# printer_control.net
KiCad netlist of a schematic drawn in Altium Designer
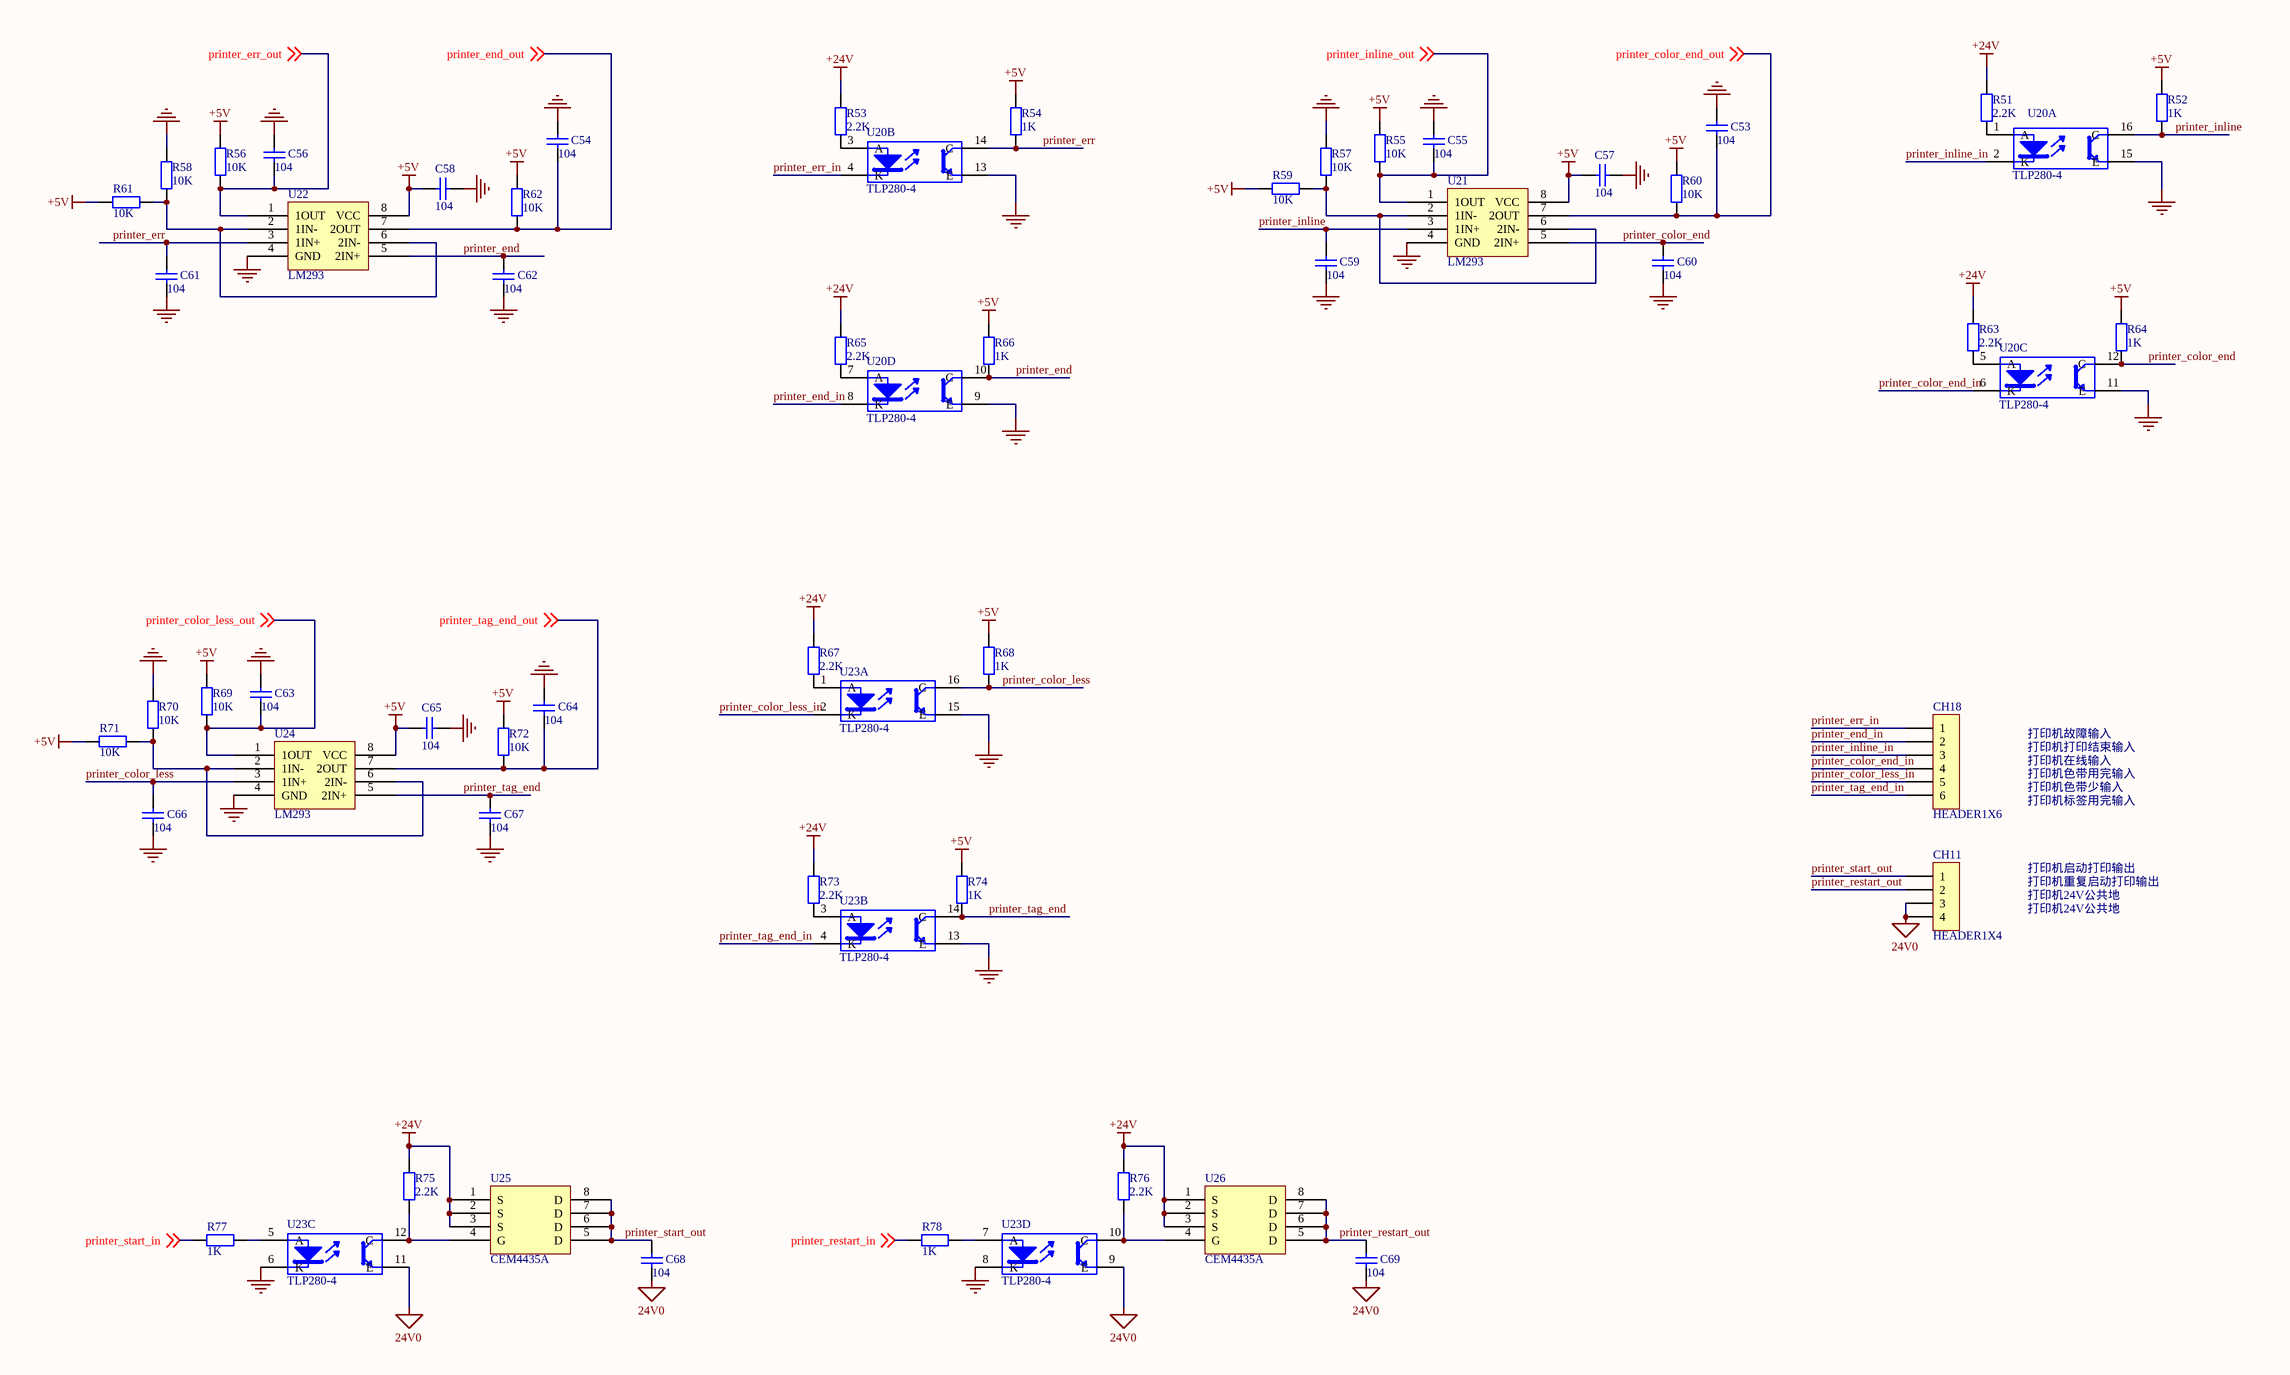
[diagram p0: printer_control.SchDoc]

(export (version "E")
  (design (tool "Eeschema 10.0.6"))
  (components
    (comp (ref "C53")
      (value "104")
      (footprint "0805")
      (description "Capacitor")
      (fields (field (name "Comment") "Cap") (field (name "PUBLISHER") "Altium Limited"))
      (libsource (lib "Miscellaneous Devices") (part "Cap"))
    )
    (comp (ref "C54")
      (value "104")
      (footprint "0805")
      (description "Capacitor")
      (fields (field (name "Comment") "Cap") (field (name "PUBLISHER") "Altium Limited"))
      (libsource (lib "Miscellaneous Devices") (part "Cap"))
    )
    (comp (ref "C55")
      (value "104")
      (footprint "0805")
      (description "Capacitor")
      (fields (field (name "Comment") "Cap") (field (name "PUBLISHER") "Altium Limited"))
      (libsource (lib "Miscellaneous Devices") (part "Cap"))
    )
    (comp (ref "C56")
      (value "104")
      (footprint "0805")
      (description "Capacitor")
      (fields (field (name "Comment") "Cap") (field (name "PUBLISHER") "Altium Limited"))
      (libsource (lib "Miscellaneous Devices") (part "Cap"))
    )
    (comp (ref "C57")
      (value "104")
      (footprint "0805")
      (description "Capacitor")
      (fields (field (name "Comment") "Cap") (field (name "PUBLISHER") "Altium Limited"))
      (libsource (lib "Miscellaneous Devices") (part "Cap"))
    )
    (comp (ref "C58")
      (value "104")
      (footprint "0805")
      (description "Capacitor")
      (fields (field (name "Comment") "Cap") (field (name "PUBLISHER") "Altium Limited"))
      (libsource (lib "Miscellaneous Devices") (part "Cap"))
    )
    (comp (ref "C59")
      (value "104")
      (footprint "0805")
      (description "Capacitor")
      (fields (field (name "Comment") "Cap") (field (name "PUBLISHER") "Altium Limited"))
      (libsource (lib "Miscellaneous Devices") (part "Cap"))
    )
    (comp (ref "C60")
      (value "104")
      (footprint "0805")
      (description "Capacitor")
      (fields (field (name "Comment") "Cap") (field (name "PUBLISHER") "Altium Limited"))
      (libsource (lib "Miscellaneous Devices") (part "Cap"))
    )
    (comp (ref "C61")
      (value "104")
      (footprint "0805")
      (description "Capacitor")
      (fields (field (name "Comment") "Cap") (field (name "PUBLISHER") "Altium Limited"))
      (libsource (lib "Miscellaneous Devices") (part "Cap"))
    )
    (comp (ref "C62")
      (value "104")
      (footprint "0805")
      (description "Capacitor")
      (fields (field (name "Comment") "Cap") (field (name "PUBLISHER") "Altium Limited"))
      (libsource (lib "Miscellaneous Devices") (part "Cap"))
    )
    (comp (ref "C63")
      (value "104")
      (footprint "0805")
      (description "Capacitor")
      (fields (field (name "Comment") "Cap") (field (name "PUBLISHER") "Altium Limited"))
      (libsource (lib "Miscellaneous Devices") (part "Cap"))
    )
    (comp (ref "C64")
      (value "104")
      (footprint "0805")
      (description "Capacitor")
      (fields (field (name "Comment") "Cap") (field (name "PUBLISHER") "Altium Limited"))
      (libsource (lib "Miscellaneous Devices") (part "Cap"))
    )
    (comp (ref "C65")
      (value "104")
      (footprint "0805")
      (description "Capacitor")
      (fields (field (name "Comment") "Cap") (field (name "PUBLISHER") "Altium Limited"))
      (libsource (lib "Miscellaneous Devices") (part "Cap"))
    )
    (comp (ref "C66")
      (value "104")
      (footprint "0805")
      (description "Capacitor")
      (fields (field (name "Comment") "Cap") (field (name "PUBLISHER") "Altium Limited"))
      (libsource (lib "Miscellaneous Devices") (part "Cap"))
    )
    (comp (ref "C67")
      (value "104")
      (footprint "0805")
      (description "Capacitor")
      (fields (field (name "Comment") "Cap") (field (name "PUBLISHER") "Altium Limited"))
      (libsource (lib "Miscellaneous Devices") (part "Cap"))
    )
    (comp (ref "C68")
      (value "104")
      (footprint "0805")
      (description "Capacitor")
      (fields (field (name "Comment") "Cap") (field (name "PUBLISHER") "Altium Limited"))
      (libsource (lib "Miscellaneous Devices") (part "Cap"))
    )
    (comp (ref "C69")
      (value "104")
      (footprint "0805")
      (description "Capacitor")
      (fields (field (name "Comment") "Cap") (field (name "PUBLISHER") "Altium Limited"))
      (libsource (lib "Miscellaneous Devices") (part "Cap"))
    )
    (comp (ref "CH11")
      (value "HEADER1X4")
      (footprint "CH3.96-4PIN")
      (libsource (lib "myIntegrated_Library1") (part "HEADER1X4"))
    )
    (comp (ref "CH18")
      (value "HEADER1X6")
      (footprint "CH3.96-6PIN")
      (libsource (lib "myIntegrated_Library1") (part "HEADER1X6"))
    )
    (comp (ref "R51")
      (value "2.2K")
      (footprint "0805")
      (description "Resistor")
      (fields (field (name "Comment") "Res2") (field (name "PUBLISHER") "Altium Limited"))
      (libsource (lib "") (part "Res2_1"))
    )
    (comp (ref "R52")
      (value "1K")
      (footprint "0805")
      (description "Resistor")
      (fields (field (name "Comment") "Res2") (field (name "PUBLISHER") "Altium Limited"))
      (libsource (lib "") (part "Res2_1"))
    )
    (comp (ref "R53")
      (value "2.2K")
      (footprint "0805")
      (description "Resistor")
      (fields (field (name "Comment") "Res2") (field (name "PUBLISHER") "Altium Limited"))
      (libsource (lib "") (part "Res2_1"))
    )
    (comp (ref "R54")
      (value "1K")
      (footprint "0805")
      (description "Resistor")
      (fields (field (name "Comment") "Res2") (field (name "PUBLISHER") "Altium Limited"))
      (libsource (lib "") (part "Res2_1"))
    )
    (comp (ref "R55")
      (value "10K")
      (footprint "0805")
      (description "Resistor")
      (fields (field (name "Comment") "Res2") (field (name "PUBLISHER") "Altium Limited"))
      (libsource (lib "") (part "Res2_1"))
    )
    (comp (ref "R56")
      (value "10K")
      (footprint "0805")
      (description "Resistor")
      (fields (field (name "Comment") "Res2") (field (name "PUBLISHER") "Altium Limited"))
      (libsource (lib "") (part "Res2_1"))
    )
    (comp (ref "R57")
      (value "10K")
      (footprint "0805")
      (description "Resistor")
      (fields (field (name "Comment") "Res2") (field (name "PUBLISHER") "Altium Limited"))
      (libsource (lib "") (part "Res2_1"))
    )
    (comp (ref "R58")
      (value "10K")
      (footprint "0805")
      (description "Resistor")
      (fields (field (name "Comment") "Res2") (field (name "PUBLISHER") "Altium Limited"))
      (libsource (lib "") (part "Res2_1"))
    )
    (comp (ref "R59")
      (value "10K")
      (footprint "0805")
      (description "Resistor")
      (fields (field (name "Comment") "Res2") (field (name "PUBLISHER") "Altium Limited"))
      (libsource (lib "Miscellaneous Devices") (part "Res2"))
    )
    (comp (ref "R60")
      (value "10K")
      (footprint "0805")
      (description "Resistor")
      (fields (field (name "Comment") "Res2") (field (name "PUBLISHER") "Altium Limited"))
      (libsource (lib "") (part "Res2_1"))
    )
    (comp (ref "R61")
      (value "10K")
      (footprint "0805")
      (description "Resistor")
      (fields (field (name "Comment") "Res2") (field (name "PUBLISHER") "Altium Limited"))
      (libsource (lib "Miscellaneous Devices") (part "Res2"))
    )
    (comp (ref "R62")
      (value "10K")
      (footprint "0805")
      (description "Resistor")
      (fields (field (name "Comment") "Res2") (field (name "PUBLISHER") "Altium Limited"))
      (libsource (lib "") (part "Res2_1"))
    )
    (comp (ref "R63")
      (value "2.2K")
      (footprint "0805")
      (description "Resistor")
      (fields (field (name "Comment") "Res2") (field (name "PUBLISHER") "Altium Limited"))
      (libsource (lib "") (part "Res2_1"))
    )
    (comp (ref "R64")
      (value "1K")
      (footprint "0805")
      (description "Resistor")
      (fields (field (name "Comment") "Res2") (field (name "PUBLISHER") "Altium Limited"))
      (libsource (lib "") (part "Res2_1"))
    )
    (comp (ref "R65")
      (value "2.2K")
      (footprint "0805")
      (description "Resistor")
      (fields (field (name "Comment") "Res2") (field (name "PUBLISHER") "Altium Limited"))
      (libsource (lib "") (part "Res2_1"))
    )
    (comp (ref "R66")
      (value "1K")
      (footprint "0805")
      (description "Resistor")
      (fields (field (name "Comment") "Res2") (field (name "PUBLISHER") "Altium Limited"))
      (libsource (lib "") (part "Res2_1"))
    )
    (comp (ref "R67")
      (value "2.2K")
      (footprint "0805")
      (description "Resistor")
      (fields (field (name "Comment") "Res2") (field (name "PUBLISHER") "Altium Limited"))
      (libsource (lib "") (part "Res2_1"))
    )
    (comp (ref "R68")
      (value "1K")
      (footprint "0805")
      (description "Resistor")
      (fields (field (name "Comment") "Res2") (field (name "PUBLISHER") "Altium Limited"))
      (libsource (lib "") (part "Res2_1"))
    )
    (comp (ref "R69")
      (value "10K")
      (footprint "0805")
      (description "Resistor")
      (fields (field (name "Comment") "Res2") (field (name "PUBLISHER") "Altium Limited"))
      (libsource (lib "") (part "Res2_1"))
    )
    (comp (ref "R70")
      (value "10K")
      (footprint "0805")
      (description "Resistor")
      (fields (field (name "Comment") "Res2") (field (name "PUBLISHER") "Altium Limited"))
      (libsource (lib "") (part "Res2_1"))
    )
    (comp (ref "R71")
      (value "10K")
      (footprint "0805")
      (description "Resistor")
      (fields (field (name "Comment") "Res2") (field (name "PUBLISHER") "Altium Limited"))
      (libsource (lib "Miscellaneous Devices") (part "Res2"))
    )
    (comp (ref "R72")
      (value "10K")
      (footprint "0805")
      (description "Resistor")
      (fields (field (name "Comment") "Res2") (field (name "PUBLISHER") "Altium Limited"))
      (libsource (lib "") (part "Res2_1"))
    )
    (comp (ref "R73")
      (value "2.2K")
      (footprint "0805")
      (description "Resistor")
      (fields (field (name "Comment") "Res2") (field (name "PUBLISHER") "Altium Limited"))
      (libsource (lib "") (part "Res2_1"))
    )
    (comp (ref "R74")
      (value "1K")
      (footprint "0805")
      (description "Resistor")
      (fields (field (name "Comment") "Res2") (field (name "PUBLISHER") "Altium Limited"))
      (libsource (lib "") (part "Res2_1"))
    )
    (comp (ref "R75")
      (value "2.2K")
      (footprint "0805")
      (description "Resistor")
      (fields (field (name "Comment") "Res2") (field (name "PUBLISHER") "Altium Limited"))
      (libsource (lib "") (part "Res2_1"))
    )
    (comp (ref "R76")
      (value "2.2K")
      (footprint "0805")
      (description "Resistor")
      (fields (field (name "Comment") "Res2") (field (name "PUBLISHER") "Altium Limited"))
      (libsource (lib "") (part "Res2_1"))
    )
    (comp (ref "R77")
      (value "1K")
      (footprint "0805")
      (description "Resistor")
      (fields (field (name "Comment") "Res2") (field (name "PUBLISHER") "Altium Limited"))
      (libsource (lib "Miscellaneous Devices") (part "Res2"))
    )
    (comp (ref "R78")
      (value "1K")
      (footprint "0805")
      (description "Resistor")
      (fields (field (name "Comment") "Res2") (field (name "PUBLISHER") "Altium Limited"))
      (libsource (lib "Miscellaneous Devices") (part "Res2"))
    )
    (comp (ref "U20") (value "TLP280-4") (footprint "SO16") (libsource (lib "WH V20") (part "TLP521-4")))
    (comp (ref "U21")
      (value "LM293")
      (footprint "SOP8-OP27")
      (libsource (lib "myIntegrated_Library1") (part "LM293"))
    )
    (comp (ref "U22")
      (value "LM293")
      (footprint "SOP8-OP27")
      (libsource (lib "myIntegrated_Library1") (part "LM293"))
    )
    (comp (ref "U23") (value "TLP280-4") (footprint "SO16") (libsource (lib "WH V20") (part "TLP521-4")))
    (comp (ref "U24")
      (value "LM293")
      (footprint "SOP8-OP27")
      (libsource (lib "myIntegrated_Library1") (part "LM293"))
    )
    (comp (ref "U25")
      (value "CEM4435A")
      (footprint "SOP8-OP27")
      (libsource (lib "myIntegrated_Library1") (part "CEM4435A"))
    )
    (comp (ref "U26")
      (value "CEM4435A")
      (footprint "SOP8-OP27")
      (libsource (lib "myIntegrated_Library1") (part "CEM4435A"))
    )
  )
  (nets
    (net (code "1") (name "+5V") (class "Default")
      (node (ref "C57") (pin "2") (pinfunction "2_2") (pintype "passive"))
      (node (ref "C58") (pin "2") (pinfunction "2_2") (pintype "passive"))
      (node (ref "C65") (pin "2") (pinfunction "2_2") (pintype "passive"))
      (node (ref "R52") (pin "1") (pinfunction "1_1") (pintype "passive"))
      (node (ref "R54") (pin "1") (pinfunction "1_1") (pintype "passive"))
      (node (ref "R55") (pin "1") (pinfunction "1_1") (pintype "passive"))
      (node (ref "R56") (pin "1") (pinfunction "1_1") (pintype "passive"))
      (node (ref "R59") (pin "1") (pinfunction "1_1") (pintype "passive"))
      (node (ref "R60") (pin "1") (pinfunction "1_1") (pintype "passive"))
      (node (ref "R61") (pin "1") (pinfunction "1_1") (pintype "passive"))
      (node (ref "R62") (pin "1") (pinfunction "1_1") (pintype "passive"))
      (node (ref "R64") (pin "1") (pinfunction "1_1") (pintype "passive"))
      (node (ref "R66") (pin "1") (pinfunction "1_1") (pintype "passive"))
      (node (ref "R68") (pin "1") (pinfunction "1_1") (pintype "passive"))
      (node (ref "R69") (pin "1") (pinfunction "1_1") (pintype "passive"))
      (node (ref "R71") (pin "1") (pinfunction "1_1") (pintype "passive"))
      (node (ref "R72") (pin "1") (pinfunction "1_1") (pintype "passive"))
      (node (ref "R74") (pin "1") (pinfunction "1_1") (pintype "passive"))
      (node (ref "U21") (pin "8") (pinfunction "VCC_8") (pintype "passive"))
      (node (ref "U22") (pin "8") (pinfunction "VCC_8") (pintype "passive"))
      (node (ref "U24") (pin "8") (pinfunction "VCC_8") (pintype "passive"))
    )
    (net (code "2") (name "+24V") (class "Default")
      (node (ref "R51") (pin "1") (pinfunction "1_1") (pintype "passive"))
      (node (ref "R53") (pin "1") (pinfunction "1_1") (pintype "passive"))
      (node (ref "R63") (pin "1") (pinfunction "1_1") (pintype "passive"))
      (node (ref "R65") (pin "1") (pinfunction "1_1") (pintype "passive"))
      (node (ref "R67") (pin "1") (pinfunction "1_1") (pintype "passive"))
      (node (ref "R73") (pin "1") (pinfunction "1_1") (pintype "passive"))
      (node (ref "R75") (pin "1") (pinfunction "1_1") (pintype "passive"))
      (node (ref "R76") (pin "1") (pinfunction "1_1") (pintype "passive"))
      (node (ref "U25") (pin "1") (pinfunction "S_1") (pintype "passive"))
      (node (ref "U25") (pin "2") (pinfunction "S_2") (pintype "passive"))
      (node (ref "U25") (pin "3") (pinfunction "S_3") (pintype "passive"))
      (node (ref "U26") (pin "1") (pinfunction "S_1") (pintype "passive"))
      (node (ref "U26") (pin "2") (pinfunction "S_2") (pintype "passive"))
      (node (ref "U26") (pin "3") (pinfunction "S_3") (pintype "passive"))
    )
    (net (code "3") (name "/printer_color_end") (class "Default")
      (node (ref "C60") (pin "2") (pinfunction "2_2") (pintype "passive"))
      (node (ref "R64") (pin "2") (pinfunction "2_2") (pintype "passive"))
      (node (ref "U20") (pin "12") (pinfunction "C_12") (pintype "passive"))
      (node (ref "U21") (pin "5") (pinfunction "2IN+_5") (pintype "passive"))
    )
    (net (code "4") (name "/printer_color_end_in") (class "Default")
      (node (ref "CH18") (pin "4") (pinfunction "4_4") (pintype "passive"))
      (node (ref "U20") (pin "6") (pinfunction "K_6") (pintype "passive"))
    )
    (net (code "5") (name "/printer_color_less") (class "Default")
      (node (ref "C66") (pin "2") (pinfunction "2_2") (pintype "passive"))
      (node (ref "R68") (pin "2") (pinfunction "2_2") (pintype "passive"))
      (node (ref "U23") (pin "16") (pinfunction "C_16") (pintype "passive"))
      (node (ref "U24") (pin "3") (pinfunction "1IN+_3") (pintype "passive"))
    )
    (net (code "6") (name "/printer_color_less_in") (class "Default")
      (node (ref "CH18") (pin "5") (pinfunction "5_5") (pintype "passive"))
      (node (ref "U23") (pin "2") (pinfunction "K_2") (pintype "passive"))
    )
    (net (code "7") (name "/printer_end") (class "Default")
      (node (ref "C62") (pin "2") (pinfunction "2_2") (pintype "passive"))
      (node (ref "R66") (pin "2") (pinfunction "2_2") (pintype "passive"))
      (node (ref "U20") (pin "10") (pinfunction "C_10") (pintype "passive"))
      (node (ref "U22") (pin "5") (pinfunction "2IN+_5") (pintype "passive"))
    )
    (net (code "8") (name "/printer_end_in") (class "Default")
      (node (ref "CH18") (pin "2") (pinfunction "2_2") (pintype "passive"))
      (node (ref "U20") (pin "8") (pinfunction "K_8") (pintype "passive"))
    )
    (net (code "9") (name "/printer_err") (class "Default")
      (node (ref "C61") (pin "2") (pinfunction "2_2") (pintype "passive"))
      (node (ref "R54") (pin "2") (pinfunction "2_2") (pintype "passive"))
      (node (ref "U20") (pin "14") (pinfunction "C_14") (pintype "passive"))
      (node (ref "U22") (pin "3") (pinfunction "1IN+_3") (pintype "passive"))
    )
    (net (code "10") (name "/printer_err_in") (class "Default")
      (node (ref "CH18") (pin "1") (pinfunction "1_1") (pintype "passive"))
      (node (ref "U20") (pin "4") (pinfunction "K_4") (pintype "passive"))
    )
    (net (code "11") (name "/printer_inline") (class "Default")
      (node (ref "C59") (pin "2") (pinfunction "2_2") (pintype "passive"))
      (node (ref "R52") (pin "2") (pinfunction "2_2") (pintype "passive"))
      (node (ref "U20") (pin "16") (pinfunction "C_16") (pintype "passive"))
      (node (ref "U21") (pin "3") (pinfunction "1IN+_3") (pintype "passive"))
    )
    (net (code "12") (name "/printer_inline_in") (class "Default")
      (node (ref "CH18") (pin "3") (pinfunction "3_3") (pintype "passive"))
      (node (ref "U20") (pin "2") (pinfunction "K_2") (pintype "passive"))
    )
    (net (code "13") (name "/printer_restart_out") (class "Default")
      (node (ref "C69") (pin "2") (pinfunction "2_2") (pintype "passive"))
      (node (ref "CH11") (pin "2") (pinfunction "2_2") (pintype "passive"))
      (node (ref "U26") (pin "5") (pinfunction "D_5") (pintype "passive"))
      (node (ref "U26") (pin "6") (pinfunction "D_6") (pintype "passive"))
      (node (ref "U26") (pin "7") (pinfunction "D_7") (pintype "passive"))
      (node (ref "U26") (pin "8") (pinfunction "D_8") (pintype "passive"))
    )
    (net (code "14") (name "/printer_start_out") (class "Default")
      (node (ref "C68") (pin "2") (pinfunction "2_2") (pintype "passive"))
      (node (ref "CH11") (pin "1") (pinfunction "1_1") (pintype "passive"))
      (node (ref "U25") (pin "5") (pinfunction "D_5") (pintype "passive"))
      (node (ref "U25") (pin "6") (pinfunction "D_6") (pintype "passive"))
      (node (ref "U25") (pin "7") (pinfunction "D_7") (pintype "passive"))
      (node (ref "U25") (pin "8") (pinfunction "D_8") (pintype "passive"))
    )
    (net (code "15") (name "/printer_tag_end") (class "Default")
      (node (ref "C67") (pin "2") (pinfunction "2_2") (pintype "passive"))
      (node (ref "R74") (pin "2") (pinfunction "2_2") (pintype "passive"))
      (node (ref "U23") (pin "14") (pinfunction "C_14") (pintype "passive"))
      (node (ref "U24") (pin "5") (pinfunction "2IN+_5") (pintype "passive"))
    )
    (net (code "16") (name "/printer_tag_end_in") (class "Default")
      (node (ref "CH18") (pin "6") (pinfunction "6_6") (pintype "passive"))
      (node (ref "U23") (pin "4") (pinfunction "K_4") (pintype "passive"))
    )
    (net (code "17") (name "24V0") (class "Default")
      (node (ref "C68") (pin "1") (pinfunction "1_1") (pintype "passive"))
      (node (ref "C69") (pin "1") (pinfunction "1_1") (pintype "passive"))
      (node (ref "CH11") (pin "3") (pinfunction "3_3") (pintype "passive"))
      (node (ref "CH11") (pin "4") (pinfunction "4_4") (pintype "passive"))
      (node (ref "U23") (pin "11") (pinfunction "E_11") (pintype "passive"))
      (node (ref "U23") (pin "9") (pinfunction "E_9") (pintype "passive"))
    )
    (net (code "18") (name "GND") (class "Default")
      (node (ref "C53") (pin "2") (pinfunction "2_2") (pintype "passive"))
      (node (ref "C54") (pin "2") (pinfunction "2_2") (pintype "passive"))
      (node (ref "C55") (pin "2") (pinfunction "2_2") (pintype "passive"))
      (node (ref "C56") (pin "2") (pinfunction "2_2") (pintype "passive"))
      (node (ref "C57") (pin "1") (pinfunction "1_1") (pintype "passive"))
      (node (ref "C58") (pin "1") (pinfunction "1_1") (pintype "passive"))
      (node (ref "C59") (pin "1") (pinfunction "1_1") (pintype "passive"))
      (node (ref "C60") (pin "1") (pinfunction "1_1") (pintype "passive"))
      (node (ref "C61") (pin "1") (pinfunction "1_1") (pintype "passive"))
      (node (ref "C62") (pin "1") (pinfunction "1_1") (pintype "passive"))
      (node (ref "C63") (pin "2") (pinfunction "2_2") (pintype "passive"))
      (node (ref "C64") (pin "2") (pinfunction "2_2") (pintype "passive"))
      (node (ref "C65") (pin "1") (pinfunction "1_1") (pintype "passive"))
      (node (ref "C66") (pin "1") (pinfunction "1_1") (pintype "passive"))
      (node (ref "C67") (pin "1") (pinfunction "1_1") (pintype "passive"))
      (node (ref "R57") (pin "1") (pinfunction "1_1") (pintype "passive"))
      (node (ref "R58") (pin "1") (pinfunction "1_1") (pintype "passive"))
      (node (ref "R70") (pin "1") (pinfunction "1_1") (pintype "passive"))
      (node (ref "U20") (pin "11") (pinfunction "E_11") (pintype "passive"))
      (node (ref "U20") (pin "13") (pinfunction "E_13") (pintype "passive"))
      (node (ref "U20") (pin "15") (pinfunction "E_15") (pintype "passive"))
      (node (ref "U20") (pin "9") (pinfunction "E_9") (pintype "passive"))
      (node (ref "U21") (pin "4") (pinfunction "GND_4") (pintype "passive"))
      (node (ref "U22") (pin "4") (pinfunction "GND_4") (pintype "passive"))
      (node (ref "U23") (pin "13") (pinfunction "E_13") (pintype "passive"))
      (node (ref "U23") (pin "15") (pinfunction "E_15") (pintype "passive"))
      (node (ref "U23") (pin "6") (pinfunction "K_6") (pintype "passive"))
      (node (ref "U23") (pin "8") (pinfunction "K_8") (pintype "passive"))
      (node (ref "U24") (pin "4") (pinfunction "GND_4") (pintype "passive"))
    )
    (net (code "19") (name "Net-(U20A-A)") (class "Default")
      (node (ref "R51") (pin "2") (pinfunction "2_2") (pintype "passive"))
      (node (ref "U20") (pin "1") (pinfunction "A_1") (pintype "passive"))
    )
    (net (code "20") (name "Net-(U20B-A)") (class "Default")
      (node (ref "R53") (pin "2") (pinfunction "2_2") (pintype "passive"))
      (node (ref "U20") (pin "3") (pinfunction "A_3") (pintype "passive"))
    )
    (net (code "21") (name "Net-(U20C-A)") (class "Default")
      (node (ref "R63") (pin "2") (pinfunction "2_2") (pintype "passive"))
      (node (ref "U20") (pin "5") (pinfunction "A_5") (pintype "passive"))
    )
    (net (code "22") (name "Net-(U20D-A)") (class "Default")
      (node (ref "R65") (pin "2") (pinfunction "2_2") (pintype "passive"))
      (node (ref "U20") (pin "7") (pinfunction "A_7") (pintype "passive"))
    )
    (net (code "23") (name "Net-(U21-1IN-)") (class "Default")
      (node (ref "R57") (pin "2") (pinfunction "2_2") (pintype "passive"))
      (node (ref "R59") (pin "2") (pinfunction "2_2") (pintype "passive"))
      (node (ref "U21") (pin "2") (pinfunction "1IN-_2") (pintype "passive"))
      (node (ref "U21") (pin "6") (pinfunction "2IN-_6") (pintype "passive"))
    )
    (net (code "24") (name "Net-(U22-1IN-)") (class "Default")
      (node (ref "R58") (pin "2") (pinfunction "2_2") (pintype "passive"))
      (node (ref "R61") (pin "2") (pinfunction "2_2") (pintype "passive"))
      (node (ref "U22") (pin "2") (pinfunction "1IN-_2") (pintype "passive"))
      (node (ref "U22") (pin "6") (pinfunction "2IN-_6") (pintype "passive"))
    )
    (net (code "25") (name "Net-(U23A-A)") (class "Default")
      (node (ref "R67") (pin "2") (pinfunction "2_2") (pintype "passive"))
      (node (ref "U23") (pin "1") (pinfunction "A_1") (pintype "passive"))
    )
    (net (code "26") (name "Net-(U23B-A)") (class "Default")
      (node (ref "R73") (pin "2") (pinfunction "2_2") (pintype "passive"))
      (node (ref "U23") (pin "3") (pinfunction "A_3") (pintype "passive"))
    )
    (net (code "27") (name "Net-(U23C-A)") (class "Default")
      (node (ref "R77") (pin "2") (pinfunction "2_2") (pintype "passive"))
      (node (ref "U23") (pin "5") (pinfunction "A_5") (pintype "passive"))
    )
    (net (code "28") (name "Net-(U23C-C)") (class "Default")
      (node (ref "R75") (pin "2") (pinfunction "2_2") (pintype "passive"))
      (node (ref "U23") (pin "12") (pinfunction "C_12") (pintype "passive"))
      (node (ref "U25") (pin "4") (pinfunction "G_4") (pintype "passive"))
    )
    (net (code "29") (name "Net-(U23D-A)") (class "Default")
      (node (ref "R78") (pin "2") (pinfunction "2_2") (pintype "passive"))
      (node (ref "U23") (pin "7") (pinfunction "A_7") (pintype "passive"))
    )
    (net (code "30") (name "Net-(U23D-C)") (class "Default")
      (node (ref "R76") (pin "2") (pinfunction "2_2") (pintype "passive"))
      (node (ref "U23") (pin "10") (pinfunction "C_10") (pintype "passive"))
      (node (ref "U26") (pin "4") (pinfunction "G_4") (pintype "passive"))
    )
    (net (code "31") (name "Net-(U24-1IN-)") (class "Default")
      (node (ref "R70") (pin "2") (pinfunction "2_2") (pintype "passive"))
      (node (ref "R71") (pin "2") (pinfunction "2_2") (pintype "passive"))
      (node (ref "U24") (pin "2") (pinfunction "1IN-_2") (pintype "passive"))
      (node (ref "U24") (pin "6") (pinfunction "2IN-_6") (pintype "passive"))
    )
    (net (code "32") (name "printer_color_end_out") (class "Default")
      (node (ref "C53") (pin "1") (pinfunction "1_1") (pintype "passive"))
      (node (ref "R60") (pin "2") (pinfunction "2_2") (pintype "passive"))
      (node (ref "U21") (pin "7") (pinfunction "2OUT_7") (pintype "passive"))
    )
    (net (code "33") (name "printer_color_less_out") (class "Default")
      (node (ref "C63") (pin "1") (pinfunction "1_1") (pintype "passive"))
      (node (ref "R69") (pin "2") (pinfunction "2_2") (pintype "passive"))
      (node (ref "U24") (pin "1") (pinfunction "1OUT_1") (pintype "passive"))
    )
    (net (code "34") (name "printer_end_out") (class "Default")
      (node (ref "C54") (pin "1") (pinfunction "1_1") (pintype "passive"))
      (node (ref "R62") (pin "2") (pinfunction "2_2") (pintype "passive"))
      (node (ref "U22") (pin "7") (pinfunction "2OUT_7") (pintype "passive"))
    )
    (net (code "35") (name "printer_err_out") (class "Default")
      (node (ref "C56") (pin "1") (pinfunction "1_1") (pintype "passive"))
      (node (ref "R56") (pin "2") (pinfunction "2_2") (pintype "passive"))
      (node (ref "U22") (pin "1") (pinfunction "1OUT_1") (pintype "passive"))
    )
    (net (code "36") (name "printer_inline_out") (class "Default")
      (node (ref "C55") (pin "1") (pinfunction "1_1") (pintype "passive"))
      (node (ref "R55") (pin "2") (pinfunction "2_2") (pintype "passive"))
      (node (ref "U21") (pin "1") (pinfunction "1OUT_1") (pintype "passive"))
    )
    (net (code "37") (name "printer_restart_in") (class "Default")
      (node (ref "R78") (pin "1") (pinfunction "1_1") (pintype "passive"))
    )
    (net (code "38") (name "printer_start_in") (class "Default")
      (node (ref "R77") (pin "1") (pinfunction "1_1") (pintype "passive"))
    )
    (net (code "39") (name "printer_tag_end_out") (class "Default")
      (node (ref "C64") (pin "1") (pinfunction "1_1") (pintype "passive"))
      (node (ref "R72") (pin "2") (pinfunction "2_2") (pintype "passive"))
      (node (ref "U24") (pin "7") (pinfunction "2OUT_7") (pintype "passive"))
    )
  )
)
